# PowerIn.net
KiCad netlist of a schematic drawn in EAGLE
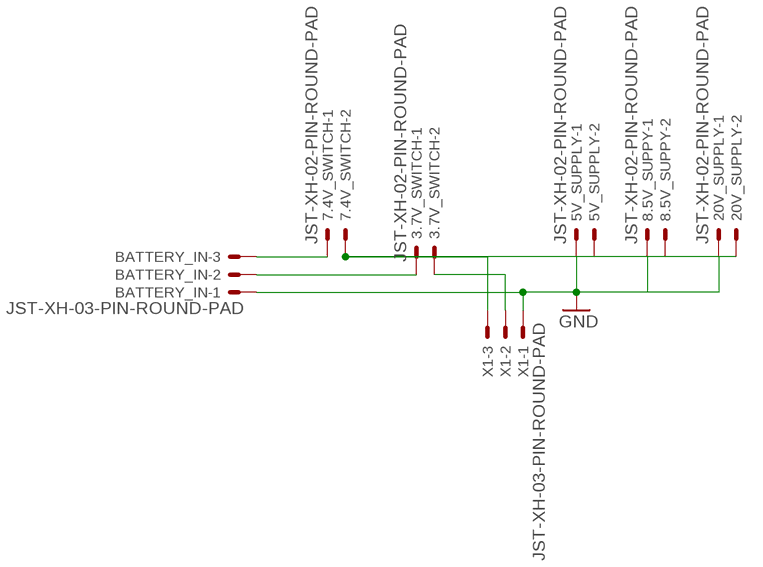
[diagram p0: schematic, sheet 1]

(export (version "E")
  (design (tool "Eeschema 10.0.6"))
  (components
    (comp (ref "3.7V_SWITCH")
      (value "JST-XH-02-PIN-ROUND-PAD")
      (footprint "eagle-import:JST-XH-02-PACKAGE-ROUND-PAD")
      (libsource (lib "eagle-import") (part "JST-XH-02-PIN-ROUND-PAD"))
    )
    (comp (ref "5V_SUPPLY")
      (value "JST-XH-02-PIN-ROUND-PAD")
      (footprint "eagle-import:JST-XH-02-PACKAGE-ROUND-PAD")
      (libsource (lib "eagle-import") (part "JST-XH-02-PIN-ROUND-PAD"))
    )
    (comp (ref "7.4V_SWITCH")
      (value "JST-XH-02-PIN-ROUND-PAD")
      (footprint "eagle-import:JST-XH-02-PACKAGE-ROUND-PAD")
      (libsource (lib "eagle-import") (part "JST-XH-02-PIN-ROUND-PAD"))
    )
    (comp (ref "8.5V_SUPPY")
      (value "JST-XH-02-PIN-ROUND-PAD")
      (footprint "eagle-import:JST-XH-02-PACKAGE-ROUND-PAD")
      (libsource (lib "eagle-import") (part "JST-XH-02-PIN-ROUND-PAD"))
    )
    (comp (ref "20V_SUPPLY")
      (value "JST-XH-02-PIN-ROUND-PAD")
      (footprint "eagle-import:JST-XH-02-PACKAGE-ROUND-PAD")
      (libsource (lib "eagle-import") (part "JST-XH-02-PIN-ROUND-PAD"))
    )
    (comp (ref "BATTERY_IN")
      (value "JST-XH-03-PIN-ROUND-PAD")
      (footprint "eagle-import:JST-XH-03-PACKAGE-ROUND-PAD")
      (libsource (lib "eagle-import") (part "JST-XH-03-PIN-ROUND-PAD"))
    )
    (comp (ref "X1")
      (value "JST-XH-03-PIN-ROUND-PAD")
      (footprint "eagle-import:JST-XH-03-PACKAGE-ROUND-PAD")
      (libsource (lib "eagle-import") (part "JST-XH-03-PIN-ROUND-PAD"))
    )
  )
  (nets
    (net (code "1") (name "GND") (class "Default")
      (node (ref "20V_SUPPLY") (pin "1") (pinfunction "S_1") (pintype "passive"))
      (node (ref "5V_SUPPLY") (pin "1") (pinfunction "S_1") (pintype "passive"))
      (node (ref "8.5V_SUPPY") (pin "1") (pinfunction "S_1") (pintype "passive"))
      (node (ref "BATTERY_IN") (pin "1") (pinfunction "S_1") (pintype "passive"))
      (node (ref "X1") (pin "1") (pinfunction "S_1") (pintype "passive"))
    )
    (net (code "2") (name "Net-(3.7V_SWITCHA-S)") (class "Default")
      (node (ref "3.7V_SWITCH") (pin "1") (pinfunction "S_1") (pintype "passive"))
      (node (ref "BATTERY_IN") (pin "2") (pinfunction "S_2") (pintype "passive"))
    )
    (net (code "3") (name "Net-(3.7V_SWITCHB-S)") (class "Default")
      (node (ref "3.7V_SWITCH") (pin "2") (pinfunction "S_2") (pintype "passive"))
      (node (ref "X1") (pin "2") (pinfunction "S_2") (pintype "passive"))
    )
    (net (code "4") (name "Net-(7.4V_SWITCHA-S)") (class "Default")
      (node (ref "7.4V_SWITCH") (pin "1") (pinfunction "S_1") (pintype "passive"))
      (node (ref "BATTERY_IN") (pin "3") (pinfunction "S_3") (pintype "passive"))
    )
    (net (code "5") (name "Net-(20V_SUPPLYB-S)") (class "Default")
      (node (ref "20V_SUPPLY") (pin "2") (pinfunction "S_2") (pintype "passive"))
      (node (ref "5V_SUPPLY") (pin "2") (pinfunction "S_2") (pintype "passive"))
      (node (ref "7.4V_SWITCH") (pin "2") (pinfunction "S_2") (pintype "passive"))
      (node (ref "8.5V_SUPPY") (pin "2") (pinfunction "S_2") (pintype "passive"))
      (node (ref "X1") (pin "3") (pinfunction "S_3") (pintype "passive"))
    )
  )
)
